# M20050-1_GPS_Breakout_Board.net
KiCad netlist of a schematic drawn in EAGLE
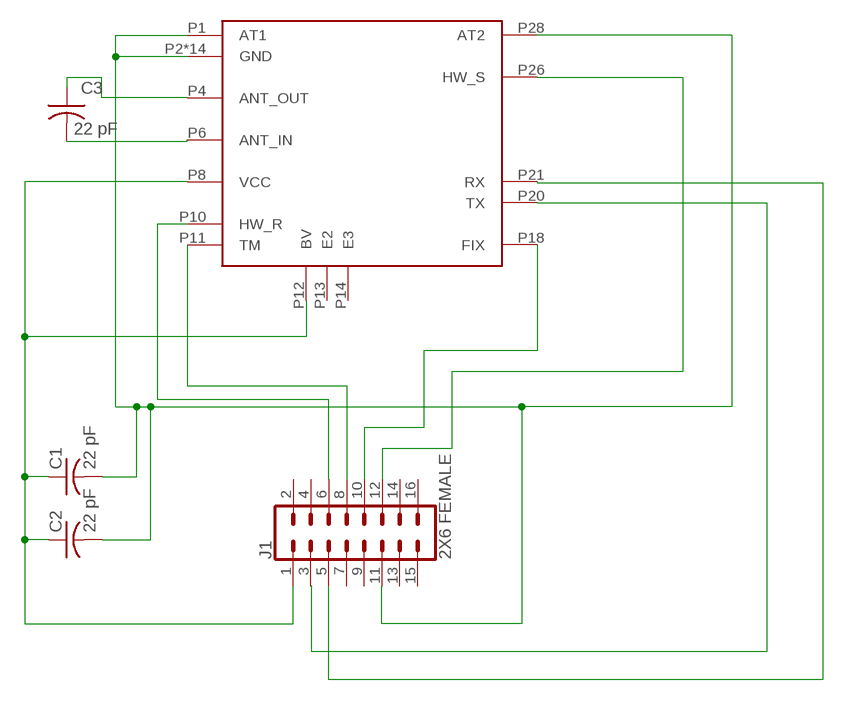
[diagram p0: schematic, sheet 1]

(export (version "E")
  (design (tool "Eeschema 10.0.6"))
  (components
    (comp (ref "A1")
      (value "GPS_M20050-1")
      (footprint "eagle-import:M20050-1_GPS")
      (libsource (lib "eagle-import") (part "GPS_M20050-1"))
    )
    (comp (ref "C1")
      (value "22 pF")
      (footprint "eagle-import:C1206")
      (libsource (lib "eagle-import") (part "C-ALL_PACKAGESC1206"))
    )
    (comp (ref "C2")
      (value "22 pF")
      (footprint "eagle-import:C1206")
      (libsource (lib "eagle-import") (part "C-ALL_PACKAGESC1206"))
    )
    (comp (ref "C3")
      (value "22 pF")
      (footprint "eagle-import:C1206")
      (libsource (lib "eagle-import") (part "C-ALL_PACKAGESC1206"))
    )
    (comp (ref "J1")
      (value "2X6 FEMALE")
      (footprint "eagle-import:2X7")
      (libsource (lib "eagle-import") (part "SENSOR_BREAKOUTPTH_FEMALE"))
    )
  )
  (nets
    (net (code "1") (name "Net-(A1-ANT_IN)") (class "Default")
      (node (ref "A1") (pin "P6") (pinfunction "ANT_IN_P6") (pintype "bidirectional"))
      (node (ref "C3") (pin "2") (pinfunction "2_2") (pintype "passive"))
    )
    (net (code "2") (name "Net-(A1-ANT_OUT)") (class "Default")
      (node (ref "A1") (pin "P4") (pinfunction "ANT_OUT_P4") (pintype "bidirectional"))
      (node (ref "C3") (pin "1") (pinfunction "1_1") (pintype "passive"))
    )
    (net (code "3") (name "Net-(A1-AT1)") (class "Default")
      (node (ref "A1") (pin "P1") (pinfunction "AT1_P1") (pintype "bidirectional"))
      (node (ref "A1") (pin "P15") (pinfunction "GND_P15") (pintype "bidirectional"))
      (node (ref "A1") (pin "P16") (pinfunction "GND_P16") (pintype "bidirectional"))
      (node (ref "A1") (pin "P17") (pinfunction "GND_P17") (pintype "bidirectional"))
      (node (ref "A1") (pin "P19") (pinfunction "GND_P19") (pintype "bidirectional"))
      (node (ref "A1") (pin "P2") (pinfunction "GND_P2") (pintype "bidirectional"))
      (node (ref "A1") (pin "P22") (pinfunction "GND_P22") (pintype "bidirectional"))
      (node (ref "A1") (pin "P23") (pinfunction "GND_P23") (pintype "bidirectional"))
      (node (ref "A1") (pin "P24") (pinfunction "GND_P24") (pintype "bidirectional"))
      (node (ref "A1") (pin "P25") (pinfunction "GND_P25") (pintype "bidirectional"))
      (node (ref "A1") (pin "P27") (pinfunction "GND_P27") (pintype "bidirectional"))
      (node (ref "A1") (pin "P28") (pinfunction "AT2_P28") (pintype "bidirectional"))
      (node (ref "A1") (pin "P3") (pinfunction "GND_P3") (pintype "bidirectional"))
      (node (ref "A1") (pin "P5") (pinfunction "GND_P5") (pintype "bidirectional"))
      (node (ref "A1") (pin "P7") (pinfunction "GND_P7") (pintype "bidirectional"))
      (node (ref "A1") (pin "P9") (pinfunction "GND_P9") (pintype "bidirectional"))
      (node (ref "C1") (pin "2") (pinfunction "2_2") (pintype "passive"))
      (node (ref "C2") (pin "2") (pinfunction "2_2") (pintype "passive"))
      (node (ref "J1") (pin "11") (pinfunction "11_11") (pintype "passive"))
    )
    (net (code "4") (name "Net-(A1-BV)") (class "Default")
      (node (ref "A1") (pin "P12") (pinfunction "BV_P12") (pintype "bidirectional"))
      (node (ref "A1") (pin "P8") (pinfunction "VCC_P8") (pintype "bidirectional"))
      (node (ref "C1") (pin "1") (pinfunction "1_1") (pintype "passive"))
      (node (ref "C2") (pin "1") (pinfunction "1_1") (pintype "passive"))
      (node (ref "J1") (pin "1") (pinfunction "1_1") (pintype "passive"))
    )
    (net (code "5") (name "Net-(A1-FIX)") (class "Default")
      (node (ref "A1") (pin "P18") (pinfunction "FIX_P18") (pintype "bidirectional"))
      (node (ref "J1") (pin "10") (pinfunction "10_10") (pintype "passive"))
    )
    (net (code "6") (name "Net-(A1-HW_R)") (class "Default")
      (node (ref "A1") (pin "P10") (pinfunction "HW_R_P10") (pintype "bidirectional"))
      (node (ref "J1") (pin "6") (pinfunction "6_6") (pintype "passive"))
    )
    (net (code "7") (name "Net-(A1-HW_S)") (class "Default")
      (node (ref "A1") (pin "P26") (pinfunction "HW_S_P26") (pintype "bidirectional"))
      (node (ref "J1") (pin "12") (pinfunction "12_12") (pintype "passive"))
    )
    (net (code "8") (name "Net-(A1-RX)") (class "Default")
      (node (ref "A1") (pin "P21") (pinfunction "RX_P21") (pintype "bidirectional"))
      (node (ref "J1") (pin "5") (pinfunction "5_5") (pintype "passive"))
    )
    (net (code "9") (name "Net-(A1-TM)") (class "Default")
      (node (ref "A1") (pin "P11") (pinfunction "TM_P11") (pintype "bidirectional"))
      (node (ref "J1") (pin "8") (pinfunction "8_8") (pintype "passive"))
    )
    (net (code "10") (name "Net-(A1-TX)") (class "Default")
      (node (ref "A1") (pin "P20") (pinfunction "TX_P20") (pintype "bidirectional"))
      (node (ref "J1") (pin "3") (pinfunction "3_3") (pintype "passive"))
    )
    (net (code "11") (name "unconnected-(A1-E2-PadP13)") (class "Default")
      (node (ref "A1") (pin "P13") (pinfunction "E2_P13") (pintype "bidirectional"))
    )
    (net (code "12") (name "unconnected-(A1-E3-PadP14)") (class "Default")
      (node (ref "A1") (pin "P14") (pinfunction "E3_P14") (pintype "bidirectional"))
    )
    (net (code "13") (name "unconnected-(J1-Pad2)") (class "Default")
      (node (ref "J1") (pin "2") (pinfunction "2_2") (pintype "passive"))
    )
    (net (code "14") (name "unconnected-(J1-Pad4)") (class "Default")
      (node (ref "J1") (pin "4") (pinfunction "4_4") (pintype "passive"))
    )
    (net (code "15") (name "unconnected-(J1-Pad7)") (class "Default")
      (node (ref "J1") (pin "7") (pinfunction "7_7") (pintype "passive"))
    )
    (net (code "16") (name "unconnected-(J1-Pad9)") (class "Default")
      (node (ref "J1") (pin "9") (pinfunction "9_9") (pintype "passive"))
    )
    (net (code "17") (name "unconnected-(J1-Pad13)") (class "Default")
      (node (ref "J1") (pin "13") (pinfunction "13_13") (pintype "passive"))
    )
    (net (code "18") (name "unconnected-(J1-Pad14)") (class "Default")
      (node (ref "J1") (pin "14") (pinfunction "14_14") (pintype "passive"))
    )
    (net (code "19") (name "unconnected-(J1-Pad15)") (class "Default")
      (node (ref "J1") (pin "15") (pinfunction "15_15") (pintype "passive"))
    )
    (net (code "20") (name "unconnected-(J1-Pad16)") (class "Default")
      (node (ref "J1") (pin "16") (pinfunction "16_16") (pintype "passive"))
    )
  )
)
